# debug.net
KiCad netlist of a schematic drawn in Altium Designer
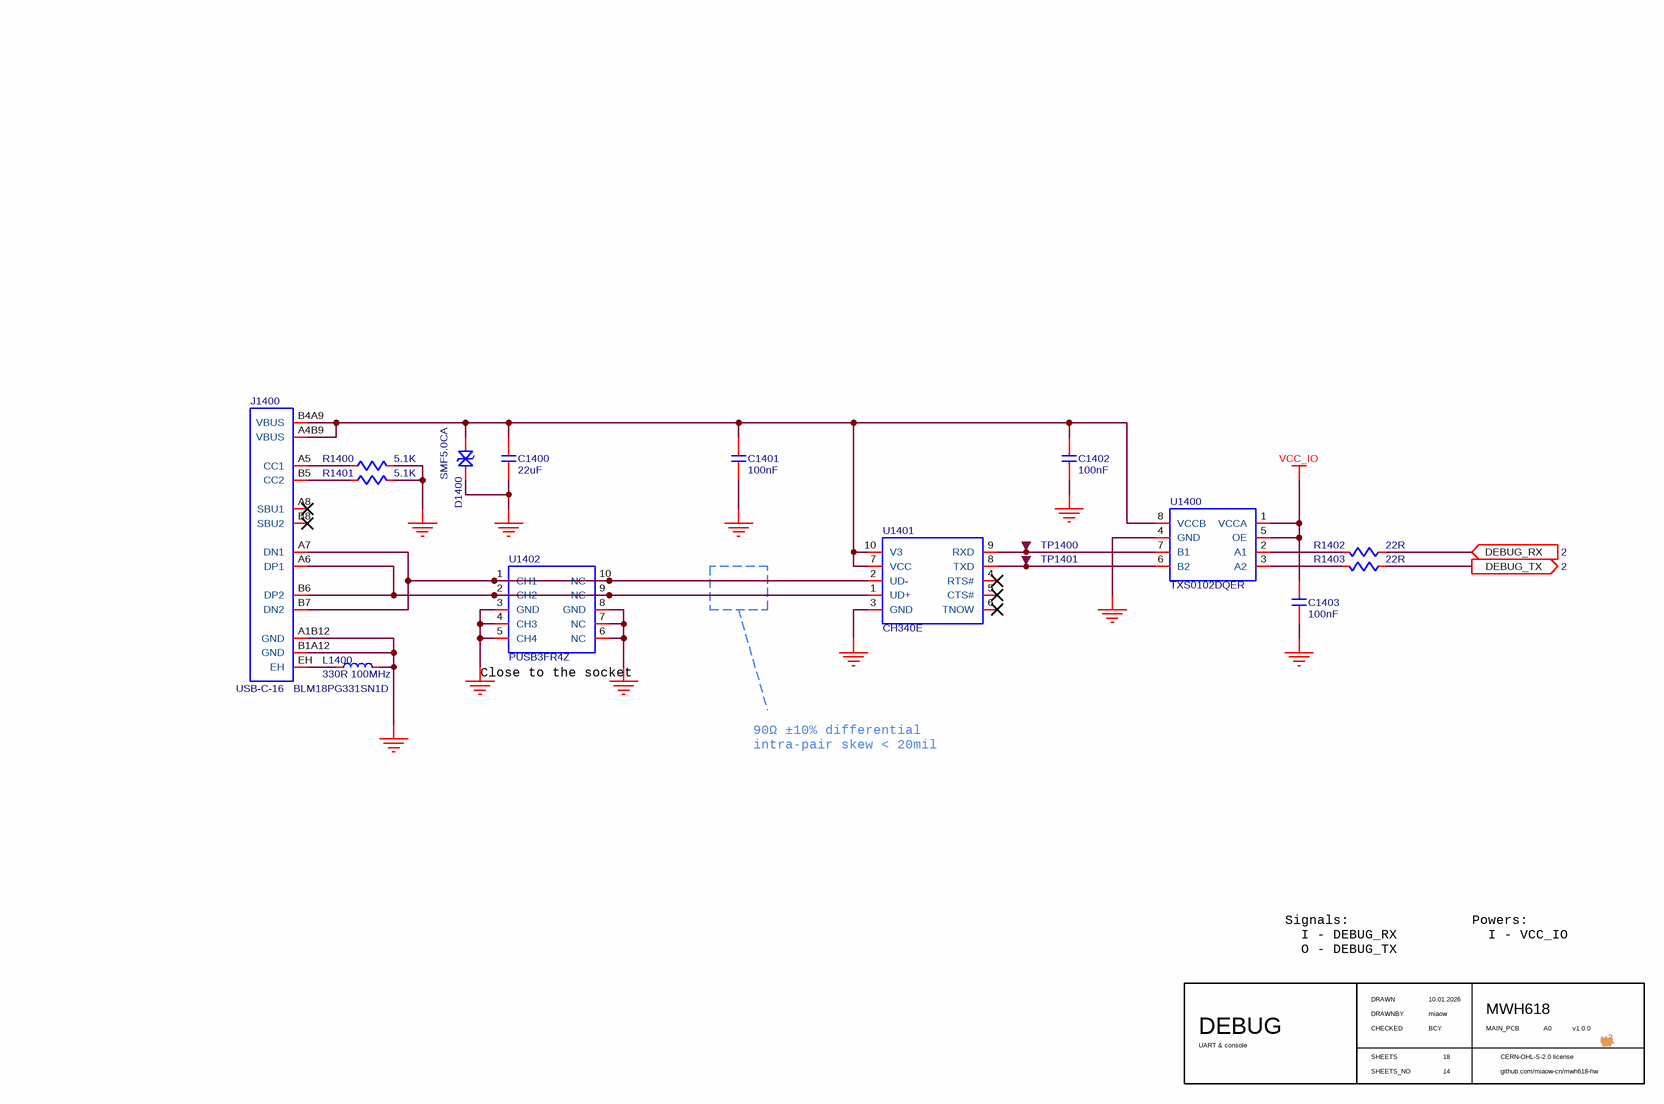
[diagram p0: debug.schdoc]

(export (version "E")
  (design (tool "Eeschema 10.0.6"))
  (components
    (comp (ref "C1400")
      (value "22uF")
      (footprint "mw:C0603")
      (fields (field (name "VOLTAGE") "10V") (field (name "Comment") "C-NOMO"))
      (libsource (lib "mw") (part "C-NOMO"))
    )
    (comp (ref "C1401")
      (value "100nF")
      (footprint "mw:C0402")
      (fields (field (name "VOLTAGE") "50V") (field (name "Comment") "C-NOMO"))
      (libsource (lib "mw") (part "C-NOMO"))
    )
    (comp (ref "C1402")
      (value "100nF")
      (footprint "mw:C0402")
      (fields (field (name "VOLTAGE") "50V") (field (name "Comment") "C-NOMO"))
      (libsource (lib "mw") (part "C-NOMO"))
    )
    (comp (ref "C1403")
      (value "100nF")
      (footprint "mw:C0402")
      (fields (field (name "VOLTAGE") "50V") (field (name "Comment") "C-NOMO"))
      (libsource (lib "mw") (part "C-NOMO"))
    )
    (comp (ref "D1400")
      (value "SMF5.0CA")
      (footprint "mw:SMF5.0CA")
      (description "TVS/ESD")
      (libsource (lib "mw") (part "SMF5.0CA"))
    )
    (comp (ref "J1400") (value "USB-C-16") (footprint "mw:USB-C-16") (libsource (lib "mw") (part "USB-C-16")))
    (comp (ref "L1400")
      (value "BLM18PG331SN1D")
      (footprint "mw:L0603")
      (fields (field (name "ALTIUM_VALUE") "330R 100MHz") (field (name "PUBLISHER") "Altium Limited"))
      (libsource (lib "mw") (part "L"))
    )
    (comp (ref "R1400")
      (value "5.1K")
      (footprint "mw:R0402")
      (fields (field (name "Comment") "R"))
      (libsource (lib "mw") (part "R"))
    )
    (comp (ref "R1401")
      (value "5.1K")
      (footprint "mw:R0402")
      (fields (field (name "Comment") "R"))
      (libsource (lib "mw") (part "R"))
    )
    (comp (ref "R1402")
      (value "22R")
      (footprint "mw:R0402")
      (fields (field (name "Comment") "R"))
      (libsource (lib "mw") (part "R"))
    )
    (comp (ref "R1403")
      (value "22R")
      (footprint "mw:R0402")
      (fields (field (name "Comment") "R"))
      (libsource (lib "mw") (part "R"))
    )
    (comp (ref "TP1400") (value "TP") (footprint "mw:TP") (libsource (lib "mw") (part "TP")))
    (comp (ref "TP1401") (value "TP") (footprint "mw:TP") (libsource (lib "mw") (part "TP")))
    (comp (ref "U1400")
      (value "TXS0102DQER")
      (footprint "mw:TXS0102DQER")
      (description "LEVEL SHIFT - 2bits, autodir, 1.65V - 3.6V, 2.3V - 5.5V, 24Mbps")
      (libsource (lib "mw") (part "TXS0102DQER"))
    )
    (comp (ref "U1401")
      (value "CH340E")
      (footprint "mw:CH340E")
      (description "USB UART")
      (libsource (lib "mw") (part "CH340E"))
    )
    (comp (ref "U1402")
      (value "PUSB3FR4Z")
      (footprint "mw:PUSB3FR4Z")
      (description "TVS/ESD - USB, HDMI")
      (libsource (lib "mw") (part "PUSB3FR4Z"))
    )
  )
  (nets
    (net (code "1") (name "/DEBUG_RX") (class "Default")
      (node (ref "R1402") (pin "2") (pinfunction "2_2") (pintype "passive"))
    )
    (net (code "2") (name "/DEBUG_TX") (class "Default")
      (node (ref "R1403") (pin "2") (pinfunction "2_2") (pintype "passive"))
    )
    (net (code "3") (name "GND") (class "Default")
      (node (ref "C1400") (pin "1") (pinfunction "1_1") (pintype "passive"))
      (node (ref "C1401") (pin "1") (pinfunction "1_1") (pintype "passive"))
      (node (ref "C1402") (pin "1") (pinfunction "1_1") (pintype "passive"))
      (node (ref "C1403") (pin "1") (pinfunction "1_1") (pintype "passive"))
      (node (ref "D1400") (pin "1") (pinfunction "1_1") (pintype "passive"))
      (node (ref "J1400") (pin "A1B12") (pinfunction "GND_A1B12") (pintype "passive"))
      (node (ref "J1400") (pin "B1A12") (pinfunction "GND_B1A12") (pintype "passive"))
      (node (ref "L1400") (pin "2") (pinfunction "2_2") (pintype "passive"))
      (node (ref "R1400") (pin "1") (pinfunction "1_1") (pintype "passive"))
      (node (ref "R1401") (pin "1") (pinfunction "1_1") (pintype "passive"))
      (node (ref "U1400") (pin "4") (pinfunction "GND_4") (pintype "passive"))
      (node (ref "U1401") (pin "3") (pinfunction "GND_3") (pintype "passive"))
      (node (ref "U1402") (pin "3") (pinfunction "GND_3") (pintype "passive"))
      (node (ref "U1402") (pin "4") (pinfunction "CH3_4") (pintype "passive"))
      (node (ref "U1402") (pin "5") (pinfunction "CH4_5") (pintype "passive"))
      (node (ref "U1402") (pin "6") (pinfunction "NC_6") (pintype "passive"))
      (node (ref "U1402") (pin "7") (pinfunction "NC_7") (pintype "passive"))
      (node (ref "U1402") (pin "8") (pinfunction "GND_8") (pintype "passive"))
    )
    (net (code "4") (name "Net-(J1400-CC1)") (class "Default")
      (node (ref "J1400") (pin "A5") (pinfunction "CC1_A5") (pintype "passive"))
      (node (ref "R1400") (pin "2") (pinfunction "2_2") (pintype "passive"))
    )
    (net (code "5") (name "Net-(J1400-CC2)") (class "Default")
      (node (ref "J1400") (pin "B5") (pinfunction "CC2_B5") (pintype "passive"))
      (node (ref "R1401") (pin "2") (pinfunction "2_2") (pintype "passive"))
    )
    (net (code "6") (name "Net-(J1400-DN1)") (class "Default")
      (node (ref "J1400") (pin "A7") (pinfunction "DN1_A7") (pintype "passive"))
      (node (ref "J1400") (pin "B7") (pinfunction "DN2_B7") (pintype "passive"))
      (node (ref "U1401") (pin "2") (pinfunction "UD-_2") (pintype "passive"))
      (node (ref "U1402") (pin "1") (pinfunction "CH1_1") (pintype "passive"))
      (node (ref "U1402") (pin "10") (pinfunction "NC_10") (pintype "passive"))
    )
    (net (code "7") (name "Net-(J1400-DP1)") (class "Default")
      (node (ref "J1400") (pin "A6") (pinfunction "DP1_A6") (pintype "passive"))
      (node (ref "J1400") (pin "B6") (pinfunction "DP2_B6") (pintype "passive"))
      (node (ref "U1401") (pin "1") (pinfunction "UD+_1") (pintype "passive"))
      (node (ref "U1402") (pin "2") (pinfunction "CH2_2") (pintype "passive"))
      (node (ref "U1402") (pin "9") (pinfunction "NC_9") (pintype "passive"))
    )
    (net (code "8") (name "Net-(J1400-PadEH)") (class "Default")
      (node (ref "J1400") (pin "EH") (pinfunction "EH_EH") (pintype "passive"))
      (node (ref "L1400") (pin "1") (pinfunction "1_1") (pintype "passive"))
    )
    (net (code "9") (name "Net-(U1400-A1)") (class "Default")
      (node (ref "R1402") (pin "1") (pinfunction "1_1") (pintype "passive"))
      (node (ref "U1400") (pin "2") (pinfunction "A1_2") (pintype "passive"))
    )
    (net (code "10") (name "Net-(U1400-A2)") (class "Default")
      (node (ref "R1403") (pin "1") (pinfunction "1_1") (pintype "passive"))
      (node (ref "U1400") (pin "3") (pinfunction "A2_3") (pintype "passive"))
    )
    (net (code "11") (name "Net-(U1400-B1)") (class "Default")
      (node (ref "TP1400") (pin "0") (pintype "passive"))
      (node (ref "U1400") (pin "7") (pinfunction "B1_7") (pintype "passive"))
      (node (ref "U1401") (pin "9") (pinfunction "RXD_9") (pintype "passive"))
    )
    (net (code "12") (name "Net-(U1400-B2)") (class "Default")
      (node (ref "TP1401") (pin "0") (pintype "passive"))
      (node (ref "U1400") (pin "6") (pinfunction "B2_6") (pintype "passive"))
      (node (ref "U1401") (pin "8") (pinfunction "TXD_8") (pintype "passive"))
    )
    (net (code "13") (name "Net-(U1400-VCCB)") (class "Default")
      (node (ref "C1400") (pin "2") (pinfunction "2_2") (pintype "passive"))
      (node (ref "C1401") (pin "2") (pinfunction "2_2") (pintype "passive"))
      (node (ref "C1402") (pin "2") (pinfunction "2_2") (pintype "passive"))
      (node (ref "D1400") (pin "2") (pinfunction "2_2") (pintype "passive"))
      (node (ref "J1400") (pin "A4B9") (pinfunction "VBUS_A4B9") (pintype "passive"))
      (node (ref "J1400") (pin "B4A9") (pinfunction "VBUS_B4A9") (pintype "passive"))
      (node (ref "U1400") (pin "8") (pinfunction "VCCB_8") (pintype "passive"))
      (node (ref "U1401") (pin "10") (pinfunction "V3_10") (pintype "passive"))
      (node (ref "U1401") (pin "7") (pinfunction "VCC_7") (pintype "passive"))
    )
    (net (code "14") (name "VCC_IO") (class "Default")
      (node (ref "C1403") (pin "2") (pinfunction "2_2") (pintype "passive"))
      (node (ref "U1400") (pin "1") (pinfunction "VCCA_1") (pintype "passive"))
      (node (ref "U1400") (pin "5") (pinfunction "OE_5") (pintype "passive"))
    )
    (net (code "15") (name "unconnected-(J1400-SBU1-PadA8)") (class "Default")
      (node (ref "J1400") (pin "A8") (pinfunction "SBU1_A8") (pintype "passive+no_connect"))
    )
    (net (code "16") (name "unconnected-(J1400-SBU2-PadB8)") (class "Default")
      (node (ref "J1400") (pin "B8") (pinfunction "SBU2_B8") (pintype "passive+no_connect"))
    )
    (net (code "17") (name "unconnected-(U1401-CTS#-Pad5)") (class "Default")
      (node (ref "U1401") (pin "5") (pinfunction "CTS#_5") (pintype "passive+no_connect"))
    )
    (net (code "18") (name "unconnected-(U1401-RTS#-Pad4)") (class "Default")
      (node (ref "U1401") (pin "4") (pinfunction "RTS#_4") (pintype "passive+no_connect"))
    )
    (net (code "19") (name "unconnected-(U1401-TNOW-Pad6)") (class "Default")
      (node (ref "U1401") (pin "6") (pinfunction "TNOW_6") (pintype "passive+no_connect"))
    )
  )
)
